# fpga12-serdes-power.net
KiCad netlist of a schematic drawn in Altium Designer
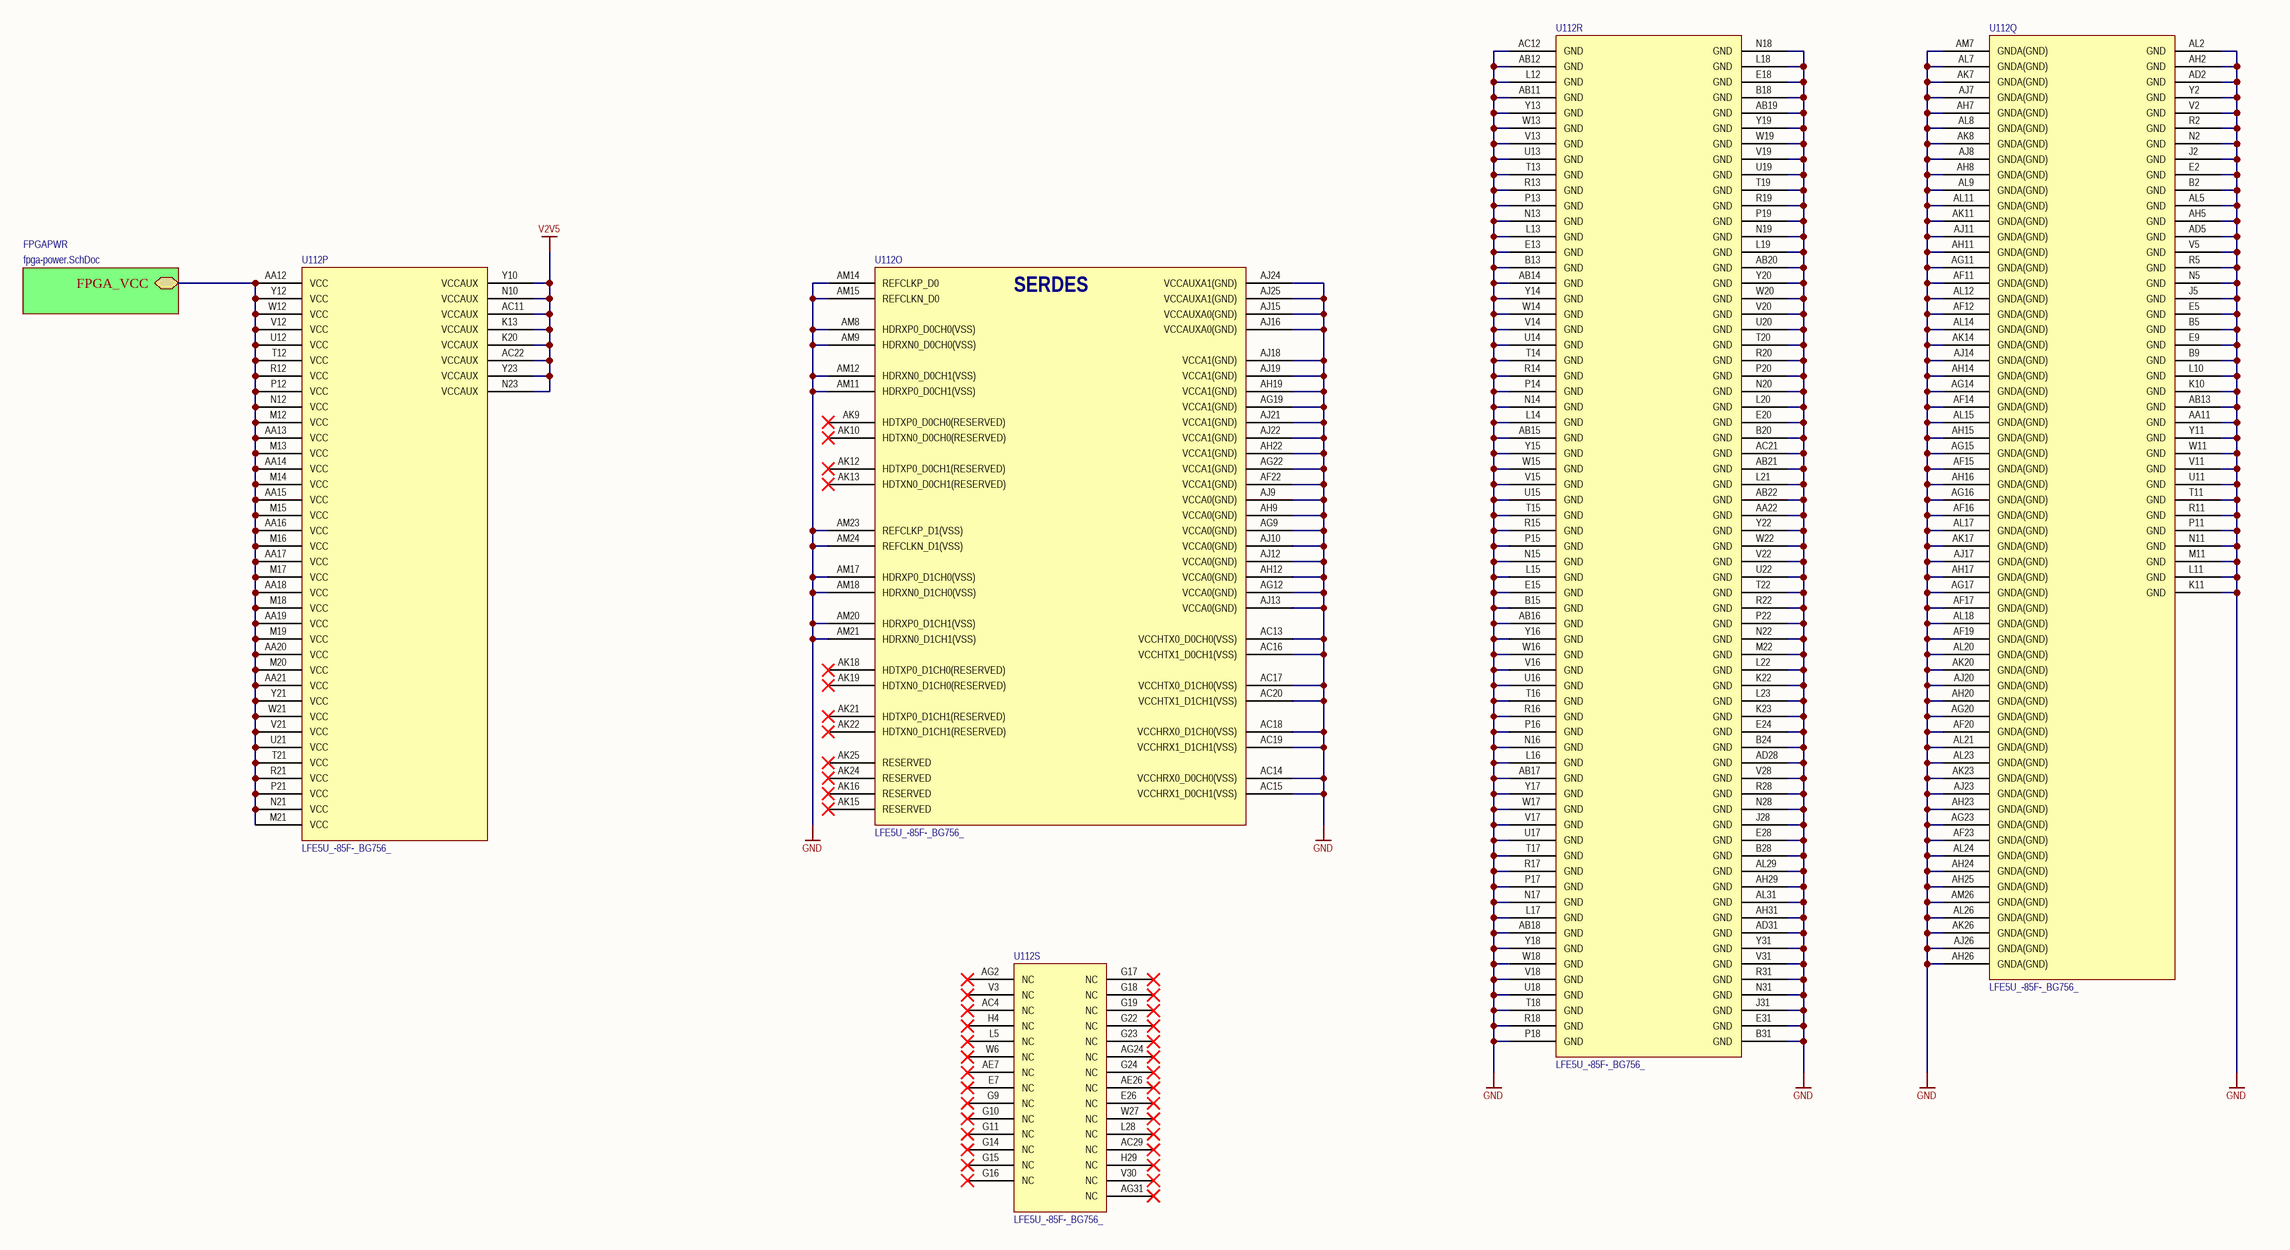
[diagram p0: fpga12-serdes-power.SchDoc]

(export (version "E")
  (design (tool "Eeschema 10.0.6"))
  (components
    (comp (ref "U112")
      (value "LFE5U_-85F-_BG756_")
      (footprint "lattice:caBGA756")
      (description "ECP5 FPGA, 85k LUT, 756-caBGA")
      (fields (field (name "MANUFACTURER") "Lattice Semiconductor"))
      (libsource (lib "lattice") (part "LFE5U_-85F-_BG756_"))
    )
  )
  (nets
    (net (code "1") (name "/FPGA_VCC") (class "Default")
      (node (ref "U112") (pin "AA12") (pinfunction "VCC_AA12") (pintype "power_in"))
      (node (ref "U112") (pin "AA13") (pinfunction "VCC_AA13") (pintype "power_in"))
      (node (ref "U112") (pin "AA14") (pinfunction "VCC_AA14") (pintype "power_in"))
      (node (ref "U112") (pin "AA15") (pinfunction "VCC_AA15") (pintype "power_in"))
      (node (ref "U112") (pin "AA16") (pinfunction "VCC_AA16") (pintype "power_in"))
      (node (ref "U112") (pin "AA17") (pinfunction "VCC_AA17") (pintype "power_in"))
      (node (ref "U112") (pin "AA18") (pinfunction "VCC_AA18") (pintype "power_in"))
      (node (ref "U112") (pin "AA19") (pinfunction "VCC_AA19") (pintype "power_in"))
      (node (ref "U112") (pin "AA20") (pinfunction "VCC_AA20") (pintype "power_in"))
      (node (ref "U112") (pin "AA21") (pinfunction "VCC_AA21") (pintype "power_in"))
      (node (ref "U112") (pin "M12") (pinfunction "VCC_M12") (pintype "power_in"))
      (node (ref "U112") (pin "M13") (pinfunction "VCC_M13") (pintype "power_in"))
      (node (ref "U112") (pin "M14") (pinfunction "VCC_M14") (pintype "power_in"))
      (node (ref "U112") (pin "M15") (pinfunction "VCC_M15") (pintype "power_in"))
      (node (ref "U112") (pin "M16") (pinfunction "VCC_M16") (pintype "power_in"))
      (node (ref "U112") (pin "M17") (pinfunction "VCC_M17") (pintype "power_in"))
      (node (ref "U112") (pin "M18") (pinfunction "VCC_M18") (pintype "power_in"))
      (node (ref "U112") (pin "M19") (pinfunction "VCC_M19") (pintype "power_in"))
      (node (ref "U112") (pin "M20") (pinfunction "VCC_M20") (pintype "power_in"))
      (node (ref "U112") (pin "M21") (pinfunction "VCC_M21") (pintype "power_in"))
      (node (ref "U112") (pin "N12") (pinfunction "VCC_N12") (pintype "power_in"))
      (node (ref "U112") (pin "N21") (pinfunction "VCC_N21") (pintype "power_in"))
      (node (ref "U112") (pin "P12") (pinfunction "VCC_P12") (pintype "power_in"))
      (node (ref "U112") (pin "P21") (pinfunction "VCC_P21") (pintype "power_in"))
      (node (ref "U112") (pin "R12") (pinfunction "VCC_R12") (pintype "power_in"))
      (node (ref "U112") (pin "R21") (pinfunction "VCC_R21") (pintype "power_in"))
      (node (ref "U112") (pin "T12") (pinfunction "VCC_T12") (pintype "power_in"))
      (node (ref "U112") (pin "T21") (pinfunction "VCC_T21") (pintype "power_in"))
      (node (ref "U112") (pin "U12") (pinfunction "VCC_U12") (pintype "power_in"))
      (node (ref "U112") (pin "U21") (pinfunction "VCC_U21") (pintype "power_in"))
      (node (ref "U112") (pin "V12") (pinfunction "VCC_V12") (pintype "power_in"))
      (node (ref "U112") (pin "V21") (pinfunction "VCC_V21") (pintype "power_in"))
      (node (ref "U112") (pin "W12") (pinfunction "VCC_W12") (pintype "power_in"))
      (node (ref "U112") (pin "W21") (pinfunction "VCC_W21") (pintype "power_in"))
      (node (ref "U112") (pin "Y12") (pinfunction "VCC_Y12") (pintype "power_in"))
      (node (ref "U112") (pin "Y21") (pinfunction "VCC_Y21") (pintype "power_in"))
    )
    (net (code "2") (name "GND") (class "Default")
      (node (ref "U112") (pin "AA11") (pinfunction "GND_AA11") (pintype "power_in"))
      (node (ref "U112") (pin "AA22") (pinfunction "GND_AA22") (pintype "power_in"))
      (node (ref "U112") (pin "AB11") (pinfunction "GND_AB11") (pintype "power_in"))
      (node (ref "U112") (pin "AB12") (pinfunction "GND_AB12") (pintype "power_in"))
      (node (ref "U112") (pin "AB13") (pinfunction "GND_AB13") (pintype "power_in"))
      (node (ref "U112") (pin "AB14") (pinfunction "GND_AB14") (pintype "power_in"))
      (node (ref "U112") (pin "AB15") (pinfunction "GND_AB15") (pintype "power_in"))
      (node (ref "U112") (pin "AB16") (pinfunction "GND_AB16") (pintype "power_in"))
      (node (ref "U112") (pin "AB17") (pinfunction "GND_AB17") (pintype "power_in"))
      (node (ref "U112") (pin "AB18") (pinfunction "GND_AB18") (pintype "power_in"))
      (node (ref "U112") (pin "AB19") (pinfunction "GND_AB19") (pintype "power_in"))
      (node (ref "U112") (pin "AB20") (pinfunction "GND_AB20") (pintype "power_in"))
      (node (ref "U112") (pin "AB21") (pinfunction "GND_AB21") (pintype "power_in"))
      (node (ref "U112") (pin "AB22") (pinfunction "GND_AB22") (pintype "power_in"))
      (node (ref "U112") (pin "AC12") (pinfunction "GND_AC12") (pintype "power_in"))
      (node (ref "U112") (pin "AC13") (pinfunction "VCCHTX0_D0CH0(VSS)_AC13") (pintype "power_in"))
      (node (ref "U112") (pin "AC14") (pinfunction "VCCHRX0_D0CH0(VSS)_AC14") (pintype "power_in"))
      (node (ref "U112") (pin "AC15") (pinfunction "VCCHRX1_D0CH1(VSS)_AC15") (pintype "power_in"))
      (node (ref "U112") (pin "AC16") (pinfunction "VCCHTX1_D0CH1(VSS)_AC16") (pintype "power_in"))
      (node (ref "U112") (pin "AC17") (pinfunction "VCCHTX0_D1CH0(VSS)_AC17") (pintype "power_in"))
      (node (ref "U112") (pin "AC18") (pinfunction "VCCHRX0_D1CH0(VSS)_AC18") (pintype "power_in"))
      (node (ref "U112") (pin "AC19") (pinfunction "VCCHRX1_D1CH1(VSS)_AC19") (pintype "power_in"))
      (node (ref "U112") (pin "AC20") (pinfunction "VCCHTX1_D1CH1(VSS)_AC20") (pintype "power_in"))
      (node (ref "U112") (pin "AC21") (pinfunction "GND_AC21") (pintype "power_in"))
      (node (ref "U112") (pin "AD2") (pinfunction "GND_AD2") (pintype "power_in"))
      (node (ref "U112") (pin "AD28") (pinfunction "GND_AD28") (pintype "power_in"))
      (node (ref "U112") (pin "AD31") (pinfunction "GND_AD31") (pintype "power_in"))
      (node (ref "U112") (pin "AD5") (pinfunction "GND_AD5") (pintype "power_in"))
      (node (ref "U112") (pin "AF11") (pinfunction "GNDA(GND)_AF11") (pintype "power_in"))
      (node (ref "U112") (pin "AF12") (pinfunction "GNDA(GND)_AF12") (pintype "power_in"))
      (node (ref "U112") (pin "AF14") (pinfunction "GNDA(GND)_AF14") (pintype "power_in"))
      (node (ref "U112") (pin "AF15") (pinfunction "GNDA(GND)_AF15") (pintype "power_in"))
      (node (ref "U112") (pin "AF16") (pinfunction "GNDA(GND)_AF16") (pintype "power_in"))
      (node (ref "U112") (pin "AF17") (pinfunction "GNDA(GND)_AF17") (pintype "power_in"))
      (node (ref "U112") (pin "AF19") (pinfunction "GNDA(GND)_AF19") (pintype "power_in"))
      (node (ref "U112") (pin "AF20") (pinfunction "GNDA(GND)_AF20") (pintype "power_in"))
      (node (ref "U112") (pin "AF22") (pinfunction "VCCA1(GND)_AF22") (pintype "power_in"))
      (node (ref "U112") (pin "AF23") (pinfunction "GNDA(GND)_AF23") (pintype "power_in"))
      (node (ref "U112") (pin "AG11") (pinfunction "GNDA(GND)_AG11") (pintype "power_in"))
      (node (ref "U112") (pin "AG12") (pinfunction "VCCA0(GND)_AG12") (pintype "power_in"))
      (node (ref "U112") (pin "AG14") (pinfunction "GNDA(GND)_AG14") (pintype "power_in"))
      (node (ref "U112") (pin "AG15") (pinfunction "GNDA(GND)_AG15") (pintype "power_in"))
      (node (ref "U112") (pin "AG16") (pinfunction "GNDA(GND)_AG16") (pintype "power_in"))
      (node (ref "U112") (pin "AG17") (pinfunction "GNDA(GND)_AG17") (pintype "power_in"))
      (node (ref "U112") (pin "AG19") (pinfunction "VCCA1(GND)_AG19") (pintype "power_in"))
      (node (ref "U112") (pin "AG20") (pinfunction "GNDA(GND)_AG20") (pintype "power_in"))
      (node (ref "U112") (pin "AG22") (pinfunction "VCCA1(GND)_AG22") (pintype "power_in"))
      (node (ref "U112") (pin "AG23") (pinfunction "GNDA(GND)_AG23") (pintype "power_in"))
      (node (ref "U112") (pin "AG9") (pinfunction "VCCA0(GND)_AG9") (pintype "power_in"))
      (node (ref "U112") (pin "AH11") (pinfunction "GNDA(GND)_AH11") (pintype "power_in"))
      (node (ref "U112") (pin "AH12") (pinfunction "VCCA0(GND)_AH12") (pintype "power_in"))
      (node (ref "U112") (pin "AH14") (pinfunction "GNDA(GND)_AH14") (pintype "power_in"))
      (node (ref "U112") (pin "AH15") (pinfunction "GNDA(GND)_AH15") (pintype "power_in"))
      (node (ref "U112") (pin "AH16") (pinfunction "GNDA(GND)_AH16") (pintype "power_in"))
      (node (ref "U112") (pin "AH17") (pinfunction "GNDA(GND)_AH17") (pintype "power_in"))
      (node (ref "U112") (pin "AH19") (pinfunction "VCCA1(GND)_AH19") (pintype "power_in"))
      (node (ref "U112") (pin "AH2") (pinfunction "GND_AH2") (pintype "power_in"))
      (node (ref "U112") (pin "AH20") (pinfunction "GNDA(GND)_AH20") (pintype "power_in"))
      (node (ref "U112") (pin "AH22") (pinfunction "VCCA1(GND)_AH22") (pintype "power_in"))
      (node (ref "U112") (pin "AH23") (pinfunction "GNDA(GND)_AH23") (pintype "power_in"))
      (node (ref "U112") (pin "AH24") (pinfunction "GNDA(GND)_AH24") (pintype "power_in"))
      (node (ref "U112") (pin "AH25") (pinfunction "GNDA(GND)_AH25") (pintype "power_in"))
      (node (ref "U112") (pin "AH26") (pinfunction "GNDA(GND)_AH26") (pintype "power_in"))
      (node (ref "U112") (pin "AH29") (pinfunction "GND_AH29") (pintype "power_in"))
      (node (ref "U112") (pin "AH31") (pinfunction "GND_AH31") (pintype "power_in"))
      (node (ref "U112") (pin "AH5") (pinfunction "GND_AH5") (pintype "power_in"))
      (node (ref "U112") (pin "AH7") (pinfunction "GNDA(GND)_AH7") (pintype "power_in"))
      (node (ref "U112") (pin "AH8") (pinfunction "GNDA(GND)_AH8") (pintype "power_in"))
      (node (ref "U112") (pin "AH9") (pinfunction "VCCA0(GND)_AH9") (pintype "power_in"))
      (node (ref "U112") (pin "AJ10") (pinfunction "VCCA0(GND)_AJ10") (pintype "power_in"))
      (node (ref "U112") (pin "AJ11") (pinfunction "GNDA(GND)_AJ11") (pintype "power_in"))
      (node (ref "U112") (pin "AJ12") (pinfunction "VCCA0(GND)_AJ12") (pintype "power_in"))
      (node (ref "U112") (pin "AJ13") (pinfunction "VCCA0(GND)_AJ13") (pintype "power_in"))
      (node (ref "U112") (pin "AJ14") (pinfunction "GNDA(GND)_AJ14") (pintype "power_in"))
      (node (ref "U112") (pin "AJ15") (pinfunction "VCCAUXA0(GND)_AJ15") (pintype "power_in"))
      (node (ref "U112") (pin "AJ16") (pinfunction "VCCAUXA0(GND)_AJ16") (pintype "power_in"))
      (node (ref "U112") (pin "AJ17") (pinfunction "GNDA(GND)_AJ17") (pintype "power_in"))
      (node (ref "U112") (pin "AJ18") (pinfunction "VCCA1(GND)_AJ18") (pintype "power_in"))
      (node (ref "U112") (pin "AJ19") (pinfunction "VCCA1(GND)_AJ19") (pintype "power_in"))
      (node (ref "U112") (pin "AJ20") (pinfunction "GNDA(GND)_AJ20") (pintype "power_in"))
      (node (ref "U112") (pin "AJ21") (pinfunction "VCCA1(GND)_AJ21") (pintype "power_in"))
      (node (ref "U112") (pin "AJ22") (pinfunction "VCCA1(GND)_AJ22") (pintype "power_in"))
      (node (ref "U112") (pin "AJ23") (pinfunction "GNDA(GND)_AJ23") (pintype "power_in"))
      (node (ref "U112") (pin "AJ24") (pinfunction "VCCAUXA1(GND)_AJ24") (pintype "power_in"))
      (node (ref "U112") (pin "AJ25") (pinfunction "VCCAUXA1(GND)_AJ25") (pintype "power_in"))
      (node (ref "U112") (pin "AJ26") (pinfunction "GNDA(GND)_AJ26") (pintype "power_in"))
      (node (ref "U112") (pin "AJ7") (pinfunction "GNDA(GND)_AJ7") (pintype "power_in"))
      (node (ref "U112") (pin "AJ8") (pinfunction "GNDA(GND)_AJ8") (pintype "power_in"))
      (node (ref "U112") (pin "AJ9") (pinfunction "VCCA0(GND)_AJ9") (pintype "power_in"))
      (node (ref "U112") (pin "AK11") (pinfunction "GNDA(GND)_AK11") (pintype "power_in"))
      (node (ref "U112") (pin "AK14") (pinfunction "GNDA(GND)_AK14") (pintype "power_in"))
      (node (ref "U112") (pin "AK17") (pinfunction "GNDA(GND)_AK17") (pintype "power_in"))
      (node (ref "U112") (pin "AK20") (pinfunction "GNDA(GND)_AK20") (pintype "power_in"))
      (node (ref "U112") (pin "AK23") (pinfunction "GNDA(GND)_AK23") (pintype "power_in"))
      (node (ref "U112") (pin "AK26") (pinfunction "GNDA(GND)_AK26") (pintype "power_in"))
      (node (ref "U112") (pin "AK7") (pinfunction "GNDA(GND)_AK7") (pintype "power_in"))
      (node (ref "U112") (pin "AK8") (pinfunction "GNDA(GND)_AK8") (pintype "power_in"))
      (node (ref "U112") (pin "AL11") (pinfunction "GNDA(GND)_AL11") (pintype "power_in"))
      (node (ref "U112") (pin "AL12") (pinfunction "GNDA(GND)_AL12") (pintype "power_in"))
      (node (ref "U112") (pin "AL14") (pinfunction "GNDA(GND)_AL14") (pintype "power_in"))
      (node (ref "U112") (pin "AL15") (pinfunction "GNDA(GND)_AL15") (pintype "power_in"))
      (node (ref "U112") (pin "AL17") (pinfunction "GNDA(GND)_AL17") (pintype "power_in"))
      (node (ref "U112") (pin "AL18") (pinfunction "GNDA(GND)_AL18") (pintype "power_in"))
      (node (ref "U112") (pin "AL2") (pinfunction "GND_AL2") (pintype "power_in"))
      (node (ref "U112") (pin "AL20") (pinfunction "GNDA(GND)_AL20") (pintype "power_in"))
      (node (ref "U112") (pin "AL21") (pinfunction "GNDA(GND)_AL21") (pintype "power_in"))
      (node (ref "U112") (pin "AL23") (pinfunction "GNDA(GND)_AL23") (pintype "power_in"))
      (node (ref "U112") (pin "AL24") (pinfunction "GNDA(GND)_AL24") (pintype "power_in"))
      (node (ref "U112") (pin "AL26") (pinfunction "GNDA(GND)_AL26") (pintype "power_in"))
      (node (ref "U112") (pin "AL29") (pinfunction "GND_AL29") (pintype "power_in"))
      (node (ref "U112") (pin "AL31") (pinfunction "GND_AL31") (pintype "power_in"))
      (node (ref "U112") (pin "AL5") (pinfunction "GND_AL5") (pintype "power_in"))
      (node (ref "U112") (pin "AL7") (pinfunction "GNDA(GND)_AL7") (pintype "power_in"))
      (node (ref "U112") (pin "AL8") (pinfunction "GNDA(GND)_AL8") (pintype "power_in"))
      (node (ref "U112") (pin "AL9") (pinfunction "GNDA(GND)_AL9") (pintype "power_in"))
      (node (ref "U112") (pin "AM11") (pinfunction "HDRXP0_D0CH1(VSS)_AM11") (pintype "passive"))
      (node (ref "U112") (pin "AM12") (pinfunction "HDRXN0_D0CH1(VSS)_AM12") (pintype "passive"))
      (node (ref "U112") (pin "AM14") (pinfunction "REFCLKP_D0_AM14") (pintype "passive"))
      (node (ref "U112") (pin "AM15") (pinfunction "REFCLKN_D0_AM15") (pintype "passive"))
      (node (ref "U112") (pin "AM17") (pinfunction "HDRXP0_D1CH0(VSS)_AM17") (pintype "passive"))
      (node (ref "U112") (pin "AM18") (pinfunction "HDRXN0_D1CH0(VSS)_AM18") (pintype "passive"))
      (node (ref "U112") (pin "AM20") (pinfunction "HDRXP0_D1CH1(VSS)_AM20") (pintype "passive"))
      (node (ref "U112") (pin "AM21") (pinfunction "HDRXN0_D1CH1(VSS)_AM21") (pintype "passive"))
      (node (ref "U112") (pin "AM23") (pinfunction "REFCLKP_D1(VSS)_AM23") (pintype "passive"))
      (node (ref "U112") (pin "AM24") (pinfunction "REFCLKN_D1(VSS)_AM24") (pintype "passive"))
      (node (ref "U112") (pin "AM26") (pinfunction "GNDA(GND)_AM26") (pintype "power_in"))
      (node (ref "U112") (pin "AM7") (pinfunction "GNDA(GND)_AM7") (pintype "power_in"))
      (node (ref "U112") (pin "AM8") (pinfunction "HDRXP0_D0CH0(VSS)_AM8") (pintype "passive"))
      (node (ref "U112") (pin "AM9") (pinfunction "HDRXN0_D0CH0(VSS)_AM9") (pintype "passive"))
      (node (ref "U112") (pin "B13") (pinfunction "GND_B13") (pintype "power_in"))
      (node (ref "U112") (pin "B15") (pinfunction "GND_B15") (pintype "power_in"))
      (node (ref "U112") (pin "B18") (pinfunction "GND_B18") (pintype "power_in"))
      (node (ref "U112") (pin "B2") (pinfunction "GND_B2") (pintype "power_in"))
      (node (ref "U112") (pin "B20") (pinfunction "GND_B20") (pintype "power_in"))
      (node (ref "U112") (pin "B24") (pinfunction "GND_B24") (pintype "power_in"))
      (node (ref "U112") (pin "B28") (pinfunction "GND_B28") (pintype "power_in"))
      (node (ref "U112") (pin "B31") (pinfunction "GND_B31") (pintype "power_in"))
      (node (ref "U112") (pin "B5") (pinfunction "GND_B5") (pintype "power_in"))
      (node (ref "U112") (pin "B9") (pinfunction "GND_B9") (pintype "power_in"))
      (node (ref "U112") (pin "E13") (pinfunction "GND_E13") (pintype "power_in"))
      (node (ref "U112") (pin "E15") (pinfunction "GND_E15") (pintype "power_in"))
      (node (ref "U112") (pin "E18") (pinfunction "GND_E18") (pintype "power_in"))
      (node (ref "U112") (pin "E2") (pinfunction "GND_E2") (pintype "power_in"))
      (node (ref "U112") (pin "E20") (pinfunction "GND_E20") (pintype "power_in"))
      (node (ref "U112") (pin "E24") (pinfunction "GND_E24") (pintype "power_in"))
      (node (ref "U112") (pin "E28") (pinfunction "GND_E28") (pintype "power_in"))
      (node (ref "U112") (pin "E31") (pinfunction "GND_E31") (pintype "power_in"))
      (node (ref "U112") (pin "E5") (pinfunction "GND_E5") (pintype "power_in"))
      (node (ref "U112") (pin "E9") (pinfunction "GND_E9") (pintype "power_in"))
      (node (ref "U112") (pin "J2") (pinfunction "GND_J2") (pintype "power_in"))
      (node (ref "U112") (pin "J28") (pinfunction "GND_J28") (pintype "power_in"))
      (node (ref "U112") (pin "J31") (pinfunction "GND_J31") (pintype "power_in"))
      (node (ref "U112") (pin "J5") (pinfunction "GND_J5") (pintype "power_in"))
      (node (ref "U112") (pin "K10") (pinfunction "GND_K10") (pintype "power_in"))
      (node (ref "U112") (pin "K11") (pinfunction "GND_K11") (pintype "power_in"))
      (node (ref "U112") (pin "K22") (pinfunction "GND_K22") (pintype "power_in"))
      (node (ref "U112") (pin "K23") (pinfunction "GND_K23") (pintype "power_in"))
      (node (ref "U112") (pin "L10") (pinfunction "GND_L10") (pintype "power_in"))
      (node (ref "U112") (pin "L11") (pinfunction "GND_L11") (pintype "power_in"))
      (node (ref "U112") (pin "L12") (pinfunction "GND_L12") (pintype "power_in"))
      (node (ref "U112") (pin "L13") (pinfunction "GND_L13") (pintype "power_in"))
      (node (ref "U112") (pin "L14") (pinfunction "GND_L14") (pintype "power_in"))
      (node (ref "U112") (pin "L15") (pinfunction "GND_L15") (pintype "power_in"))
      (node (ref "U112") (pin "L16") (pinfunction "GND_L16") (pintype "power_in"))
      (node (ref "U112") (pin "L17") (pinfunction "GND_L17") (pintype "power_in"))
      (node (ref "U112") (pin "L18") (pinfunction "GND_L18") (pintype "power_in"))
      (node (ref "U112") (pin "L19") (pinfunction "GND_L19") (pintype "power_in"))
      (node (ref "U112") (pin "L20") (pinfunction "GND_L20") (pintype "power_in"))
      (node (ref "U112") (pin "L21") (pinfunction "GND_L21") (pintype "power_in"))
      (node (ref "U112") (pin "L22") (pinfunction "GND_L22") (pintype "power_in"))
      (node (ref "U112") (pin "L23") (pinfunction "GND_L23") (pintype "power_in"))
      (node (ref "U112") (pin "M11") (pinfunction "GND_M11") (pintype "power_in"))
      (node (ref "U112") (pin "M22") (pinfunction "GND_M22") (pintype "power_in"))
      (node (ref "U112") (pin "N11") (pinfunction "GND_N11") (pintype "power_in"))
      (node (ref "U112") (pin "N13") (pinfunction "GND_N13") (pintype "power_in"))
      (node (ref "U112") (pin "N14") (pinfunction "GND_N14") (pintype "power_in"))
      (node (ref "U112") (pin "N15") (pinfunction "GND_N15") (pintype "power_in"))
      (node (ref "U112") (pin "N16") (pinfunction "GND_N16") (pintype "power_in"))
      (node (ref "U112") (pin "N17") (pinfunction "GND_N17") (pintype "power_in"))
      (node (ref "U112") (pin "N18") (pinfunction "GND_N18") (pintype "power_in"))
      (node (ref "U112") (pin "N19") (pinfunction "GND_N19") (pintype "power_in"))
      (node (ref "U112") (pin "N2") (pinfunction "GND_N2") (pintype "power_in"))
      (node (ref "U112") (pin "N20") (pinfunction "GND_N20") (pintype "power_in"))
      (node (ref "U112") (pin "N22") (pinfunction "GND_N22") (pintype "power_in"))
      (node (ref "U112") (pin "N28") (pinfunction "GND_N28") (pintype "power_in"))
      (node (ref "U112") (pin "N31") (pinfunction "GND_N31") (pintype "power_in"))
      (node (ref "U112") (pin "N5") (pinfunction "GND_N5") (pintype "power_in"))
      (node (ref "U112") (pin "P11") (pinfunction "GND_P11") (pintype "power_in"))
      (node (ref "U112") (pin "P13") (pinfunction "GND_P13") (pintype "power_in"))
      (node (ref "U112") (pin "P14") (pinfunction "GND_P14") (pintype "power_in"))
      (node (ref "U112") (pin "P15") (pinfunction "GND_P15") (pintype "power_in"))
      (node (ref "U112") (pin "P16") (pinfunction "GND_P16") (pintype "power_in"))
      (node (ref "U112") (pin "P17") (pinfunction "GND_P17") (pintype "power_in"))
      (node (ref "U112") (pin "P18") (pinfunction "GND_P18") (pintype "power_in"))
      (node (ref "U112") (pin "P19") (pinfunction "GND_P19") (pintype "power_in"))
      (node (ref "U112") (pin "P20") (pinfunction "GND_P20") (pintype "power_in"))
      (node (ref "U112") (pin "P22") (pinfunction "GND_P22") (pintype "power_in"))
      (node (ref "U112") (pin "R11") (pinfunction "GND_R11") (pintype "power_in"))
      (node (ref "U112") (pin "R13") (pinfunction "GND_R13") (pintype "power_in"))
      (node (ref "U112") (pin "R14") (pinfunction "GND_R14") (pintype "power_in"))
      (node (ref "U112") (pin "R15") (pinfunction "GND_R15") (pintype "power_in"))
      (node (ref "U112") (pin "R16") (pinfunction "GND_R16") (pintype "power_in"))
      (node (ref "U112") (pin "R17") (pinfunction "GND_R17") (pintype "power_in"))
      (node (ref "U112") (pin "R18") (pinfunction "GND_R18") (pintype "power_in"))
      (node (ref "U112") (pin "R19") (pinfunction "GND_R19") (pintype "power_in"))
      (node (ref "U112") (pin "R2") (pinfunction "GND_R2") (pintype "power_in"))
      (node (ref "U112") (pin "R20") (pinfunction "GND_R20") (pintype "power_in"))
      (node (ref "U112") (pin "R22") (pinfunction "GND_R22") (pintype "power_in"))
      (node (ref "U112") (pin "R28") (pinfunction "GND_R28") (pintype "power_in"))
      (node (ref "U112") (pin "R31") (pinfunction "GND_R31") (pintype "power_in"))
      (node (ref "U112") (pin "R5") (pinfunction "GND_R5") (pintype "power_in"))
      (node (ref "U112") (pin "T11") (pinfunction "GND_T11") (pintype "power_in"))
      (node (ref "U112") (pin "T13") (pinfunction "GND_T13") (pintype "power_in"))
      (node (ref "U112") (pin "T14") (pinfunction "GND_T14") (pintype "power_in"))
      (node (ref "U112") (pin "T15") (pinfunction "GND_T15") (pintype "power_in"))
      (node (ref "U112") (pin "T16") (pinfunction "GND_T16") (pintype "power_in"))
      (node (ref "U112") (pin "T17") (pinfunction "GND_T17") (pintype "power_in"))
      (node (ref "U112") (pin "T18") (pinfunction "GND_T18") (pintype "power_in"))
      (node (ref "U112") (pin "T19") (pinfunction "GND_T19") (pintype "power_in"))
      (node (ref "U112") (pin "T20") (pinfunction "GND_T20") (pintype "power_in"))
      (node (ref "U112") (pin "T22") (pinfunction "GND_T22") (pintype "power_in"))
      (node (ref "U112") (pin "U11") (pinfunction "GND_U11") (pintype "power_in"))
      (node (ref "U112") (pin "U13") (pinfunction "GND_U13") (pintype "power_in"))
      (node (ref "U112") (pin "U14") (pinfunction "GND_U14") (pintype "power_in"))
      (node (ref "U112") (pin "U15") (pinfunction "GND_U15") (pintype "power_in"))
      (node (ref "U112") (pin "U16") (pinfunction "GND_U16") (pintype "power_in"))
      (node (ref "U112") (pin "U17") (pinfunction "GND_U17") (pintype "power_in"))
      (node (ref "U112") (pin "U18") (pinfunction "GND_U18") (pintype "power_in"))
      (node (ref "U112") (pin "U19") (pinfunction "GND_U19") (pintype "power_in"))
      (node (ref "U112") (pin "U20") (pinfunction "GND_U20") (pintype "power_in"))
      (node (ref "U112") (pin "U22") (pinfunction "GND_U22") (pintype "power_in"))
      (node (ref "U112") (pin "V11") (pinfunction "GND_V11") (pintype "power_in"))
      (node (ref "U112") (pin "V13") (pinfunction "GND_V13") (pintype "power_in"))
      (node (ref "U112") (pin "V14") (pinfunction "GND_V14") (pintype "power_in"))
      (node (ref "U112") (pin "V15") (pinfunction "GND_V15") (pintype "power_in"))
      (node (ref "U112") (pin "V16") (pinfunction "GND_V16") (pintype "power_in"))
      (node (ref "U112") (pin "V17") (pinfunction "GND_V17") (pintype "power_in"))
      (node (ref "U112") (pin "V18") (pinfunction "GND_V18") (pintype "power_in"))
      (node (ref "U112") (pin "V19") (pinfunction "GND_V19") (pintype "power_in"))
      (node (ref "U112") (pin "V2") (pinfunction "GND_V2") (pintype "power_in"))
      (node (ref "U112") (pin "V20") (pinfunction "GND_V20") (pintype "power_in"))
      (node (ref "U112") (pin "V22") (pinfunction "GND_V22") (pintype "power_in"))
      (node (ref "U112") (pin "V28") (pinfunction "GND_V28") (pintype "power_in"))
      (node (ref "U112") (pin "V31") (pinfunction "GND_V31") (pintype "power_in"))
      (node (ref "U112") (pin "V5") (pinfunction "GND_V5") (pintype "power_in"))
      (node (ref "U112") (pin "W11") (pinfunction "GND_W11") (pintype "power_in"))
      (node (ref "U112") (pin "W13") (pinfunction "GND_W13") (pintype "power_in"))
      (node (ref "U112") (pin "W14") (pinfunction "GND_W14") (pintype "power_in"))
      (node (ref "U112") (pin "W15") (pinfunction "GND_W15") (pintype "power_in"))
      (node (ref "U112") (pin "W16") (pinfunction "GND_W16") (pintype "power_in"))
      (node (ref "U112") (pin "W17") (pinfunction "GND_W17") (pintype "power_in"))
      (node (ref "U112") (pin "W18") (pinfunction "GND_W18") (pintype "power_in"))
      (node (ref "U112") (pin "W19") (pinfunction "GND_W19") (pintype "power_in"))
      (node (ref "U112") (pin "W20") (pinfunction "GND_W20") (pintype "power_in"))
      (node (ref "U112") (pin "W22") (pinfunction "GND_W22") (pintype "power_in"))
      (node (ref "U112") (pin "Y11") (pinfunction "GND_Y11") (pintype "power_in"))
      (node (ref "U112") (pin "Y13") (pinfunction "GND_Y13") (pintype "power_in"))
      (node (ref "U112") (pin "Y14") (pinfunction "GND_Y14") (pintype "power_in"))
      (node (ref "U112") (pin "Y15") (pinfunction "GND_Y15") (pintype "power_in"))
      (node (ref "U112") (pin "Y16") (pinfunction "GND_Y16") (pintype "power_in"))
      (node (ref "U112") (pin "Y17") (pinfunction "GND_Y17") (pintype "power_in"))
      (node (ref "U112") (pin "Y18") (pinfunction "GND_Y18") (pintype "power_in"))
      (node (ref "U112") (pin "Y19") (pinfunction "GND_Y19") (pintype "power_in"))
      (node (ref "U112") (pin "Y2") (pinfunction "GND_Y2") (pintype "power_in"))
      (node (ref "U112") (pin "Y20") (pinfunction "GND_Y20") (pintype "power_in"))
      (node (ref "U112") (pin "Y22") (pinfunction "GND_Y22") (pintype "power_in"))
      (node (ref "U112") (pin "Y31") (pinfunction "GND_Y31") (pintype "power_in"))
    )
    (net (code "3") (name "V2V5") (class "Default")
      (node (ref "U112") (pin "AC11") (pinfunction "VCCAUX_AC11") (pintype "power_in"))
      (node (ref "U112") (pin "AC22") (pinfunction "VCCAUX_AC22") (pintype "power_in"))
      (node (ref "U112") (pin "K13") (pinfunction "VCCAUX_K13") (pintype "power_in"))
      (node (ref "U112") (pin "K20") (pinfunction "VCCAUX_K20") (pintype "power_in"))
      (node (ref "U112") (pin "N10") (pinfunction "VCCAUX_N10") (pintype "power_in"))
      (node (ref "U112") (pin "N23") (pinfunction "VCCAUX_N23") (pintype "power_in"))
      (node (ref "U112") (pin "Y10") (pinfunction "VCCAUX_Y10") (pintype "power_in"))
      (node (ref "U112") (pin "Y23") (pinfunction "VCCAUX_Y23") (pintype "power_in"))
    )
    (net (code "4") (name "unconnected-(U112O-HDTXN0_D0CH0(RESERVED)-PadAK10)") (class "Default")
      (node (ref "U112") (pin "AK10") (pinfunction "HDTXN0_D0CH0(RESERVED)_AK10") (pintype "passive+no_connect"))
    )
    (net (code "5") (name "unconnected-(U112O-HDTXN0_D0CH1(RESERVED)-PadAK13)") (class "Default")
      (node (ref "U112") (pin "AK13") (pinfunction "HDTXN0_D0CH1(RESERVED)_AK13") (pintype "passive+no_connect"))
    )
    (net (code "6") (name "unconnected-(U112O-HDTXN0_D1CH0(RESERVED)-PadAK19)") (class "Default")
      (node (ref "U112") (pin "AK19") (pinfunction "HDTXN0_D1CH0(RESERVED)_AK19") (pintype "passive+no_connect"))
    )
    (net (code "7") (name "unconnected-(U112O-HDTXN0_D1CH1(RESERVED)-PadAK22)") (class "Default")
      (node (ref "U112") (pin "AK22") (pinfunction "HDTXN0_D1CH1(RESERVED)_AK22") (pintype "passive+no_connect"))
    )
    (net (code "8") (name "unconnected-(U112O-HDTXP0_D0CH0(RESERVED)-PadAK9)") (class "Default")
      (node (ref "U112") (pin "AK9") (pinfunction "HDTXP0_D0CH0(RESERVED)_AK9") (pintype "passive+no_connect"))
    )
    (net (code "9") (name "unconnected-(U112O-HDTXP0_D0CH1(RESERVED)-PadAK12)") (class "Default")
      (node (ref "U112") (pin "AK12") (pinfunction "HDTXP0_D0CH1(RESERVED)_AK12") (pintype "passive+no_connect"))
    )
    (net (code "10") (name "unconnected-(U112O-HDTXP0_D1CH0(RESERVED)-PadAK18)") (class "Default")
      (node (ref "U112") (pin "AK18") (pinfunction "HDTXP0_D1CH0(RESERVED)_AK18") (pintype "passive+no_connect"))
    )
    (net (code "11") (name "unconnected-(U112O-HDTXP0_D1CH1(RESERVED)-PadAK21)") (class "Default")
      (node (ref "U112") (pin "AK21") (pinfunction "HDTXP0_D1CH1(RESERVED)_AK21") (pintype "passive+no_connect"))
    )
    (net (code "12") (name "unconnected-(U112O-RESERVED-PadAK15)") (class "Default")
      (node (ref "U112") (pin "AK15") (pinfunction "RESERVED_AK15") (pintype "passive+no_connect"))
    )
    (net (code "13") (name "unconnected-(U112O-RESERVED-PadAK16)") (class "Default")
      (node (ref "U112") (pin "AK16") (pinfunction "RESERVED_AK16") (pintype "passive+no_connect"))
    )
    (net (code "14") (name "unconnected-(U112O-RESERVED-PadAK24)") (class "Default")
      (node (ref "U112") (pin "AK24") (pinfunction "RESERVED_AK24") (pintype "passive+no_connect"))
    )
    (net (code "15") (name "unconnected-(U112O-RESERVED-PadAK25)") (class "Default")
      (node (ref "U112") (pin "AK25") (pinfunction "RESERVED_AK25") (pintype "passive+no_connect"))
    )
    (net (code "16") (name "unconnected-(U112S-NC-PadAC4)") (class "Default")
      (node (ref "U112") (pin "AC4") (pinfunction "NC_AC4") (pintype "passive+no_connect"))
    )
    (net (code "17") (name "unconnected-(U112S-NC-PadAC29)") (class "Default")
      (node (ref "U112") (pin "AC29") (pinfunction "NC_AC29") (pintype "passive+no_connect"))
    )
    (net (code "18") (name "unconnected-(U112S-NC-PadAE7)") (class "Default")
      (node (ref "U112") (pin "AE7") (pinfunction "NC_AE7") (pintype "passive+no_connect"))
    )
    (net (code "19") (name "unconnected-(U112S-NC-PadAE26)") (class "Default")
      (node (ref "U112") (pin "AE26") (pinfunction "NC_AE26") (pintype "passive+no_connect"))
    )
    (net (code "20") (name "unconnected-(U112S-NC-PadAG2)") (class "Default")
      (node (ref "U112") (pin "AG2") (pinfunction "NC_AG2") (pintype "passive+no_connect"))
    )
    (net (code "21") (name "unconnected-(U112S-NC-PadAG24)") (class "Default")
      (node (ref "U112") (pin "AG24") (pinfunction "NC_AG24") (pintype "passive+no_connect"))
    )
    (net (code "22") (name "unconnected-(U112S-NC-PadAG31)") (class "Default")
      (node (ref "U112") (pin "AG31") (pinfunction "NC_AG31") (pintype "passive+no_connect"))
    )
    (net (code "23") (name "unconnected-(U112S-NC-PadE7)") (class "Default")
      (node (ref "U112") (pin "E7") (pinfunction "NC_E7") (pintype "passive+no_connect"))
    )
    (net (code "24") (name "unconnected-(U112S-NC-PadE26)") (class "Default")
      (node (ref "U112") (pin "E26") (pinfunction "NC_E26") (pintype "passive+no_connect"))
    )
    (net (code "25") (name "unconnected-(U112S-NC-PadG9)") (class "Default")
      (node (ref "U112") (pin "G9") (pinfunction "NC_G9") (pintype "passive+no_connect"))
    )
    (net (code "26") (name "unconnected-(U112S-NC-PadG10)") (class "Default")
      (node (ref "U112") (pin "G10") (pinfunction "NC_G10") (pintype "passive+no_connect"))
    )
    (net (code "27") (name "unconnected-(U112S-NC-PadG11)") (class "Default")
      (node (ref "U112") (pin "G11") (pinfunction "NC_G11") (pintype "passive+no_connect"))
    )
    (net (code "28") (name "unconnected-(U112S-NC-PadG14)") (class "Default")
      (node (ref "U112") (pin "G14") (pinfunction "NC_G14") (pintype "passive+no_connect"))
    )
    (net (code "29") (name "unconnected-(U112S-NC-PadG15)") (class "Default")
      (node (ref "U112") (pin "G15") (pinfunction "NC_G15") (pintype "passive+no_connect"))
    )
    (net (code "30") (name "unconnected-(U112S-NC-PadG16)") (class "Default")
      (node (ref "U112") (pin "G16") (pinfunction "NC_G16") (pintype "passive+no_connect"))
    )
    (net (code "31") (name "unconnected-(U112S-NC-PadG17)") (class "Default")
      (node (ref "U112") (pin "G17") (pinfunction "NC_G17") (pintype "passive+no_connect"))
    )
    (net (code "32") (name "unconnected-(U112S-NC-PadG18)") (class "Default")
      (node (ref "U112") (pin "G18") (pinfunction "NC_G18") (pintype "passive+no_connect"))
    )
    (net (code "33") (name "unconnected-(U112S-NC-PadG19)") (class "Default")
      (node (ref "U112") (pin "G19") (pinfunction "NC_G19") (pintype "passive+no_connect"))
    )
    (net (code "34") (name "unconnected-(U112S-NC-PadG22)") (class "Default")
      (node (ref "U112") (pin "G22") (pinfunction "NC_G22") (pintype "passive+no_connect"))
    )
    (net (code "35") (name "unconnected-(U112S-NC-PadG23)") (class "Default")
      (node (ref "U112") (pin "G23") (pinfunction "NC_G23") (pintype "passive+no_connect"))
    )
    (net (code "36") (name "unconnected-(U112S-NC-PadG24)") (class "Default")
      (node (ref "U112") (pin "G24") (pinfunction "NC_G24") (pintype "passive+no_connect"))
    )
    (net (code "37") (name "unconnected-(U112S-NC-PadH4)") (class "Default")
      (node (ref "U112") (pin "H4") (pinfunction "NC_H4") (pintype "passive+no_connect"))
    )
    (net (code "38") (name "unconnected-(U112S-NC-PadH29)") (class "Default")
      (node (ref "U112") (pin "H29") (pinfunction "NC_H29") (pintype "passive+no_connect"))
    )
    (net (code "39") (name "unconnected-(U112S-NC-PadL5)") (class "Default")
      (node (ref "U112") (pin "L5") (pinfunction "NC_L5") (pintype "passive+no_connect"))
    )
    (net (code "40") (name "unconnected-(U112S-NC-PadL28)") (class "Default")
      (node (ref "U112") (pin "L28") (pinfunction "NC_L28") (pintype "passive+no_connect"))
    )
    (net (code "41") (name "unconnected-(U112S-NC-PadV3)") (class "Default")
      (node (ref "U112") (pin "V3") (pinfunction "NC_V3") (pintype "passive+no_connect"))
    )
    (net (code "42") (name "unconnected-(U112S-NC-PadV30)") (class "Default")
      (node (ref "U112") (pin "V30") (pinfunction "NC_V30") (pintype "passive+no_connect"))
    )
    (net (code "43") (name "unconnected-(U112S-NC-PadW6)") (class "Default")
      (node (ref "U112") (pin "W6") (pinfunction "NC_W6") (pintype "passive+no_connect"))
    )
    (net (code "44") (name "unconnected-(U112S-NC-PadW27)") (class "Default")
      (node (ref "U112") (pin "W27") (pinfunction "NC_W27") (pintype "passive+no_connect"))
    )
  )
)
